# AntHab-Micro-12i.net
KiCad netlist of a schematic drawn in EAGLE
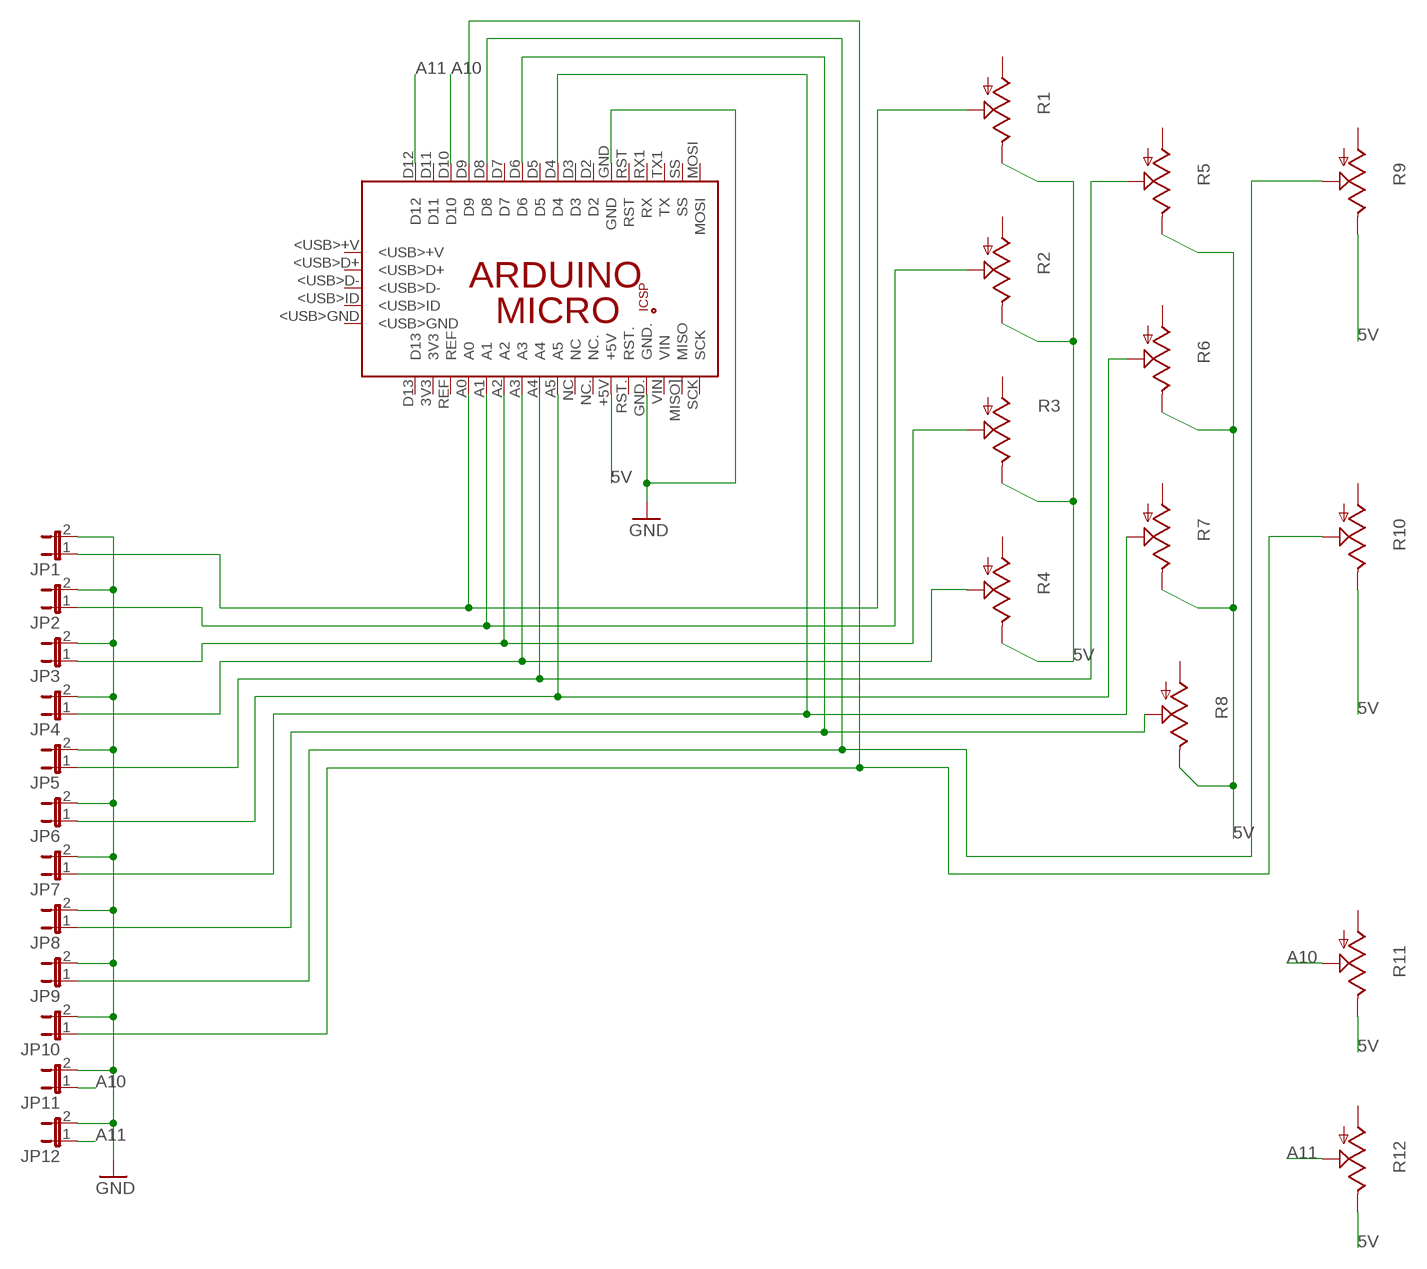
[diagram p0: schematic, sheet 1]

(export (version "E")
  (design (tool "Eeschema 10.0.6"))
  (components
    (comp (ref "JP1")
      (value "JP1E")
      (footprint "eagle-import:JP1")
      (libsource (lib "eagle-import") (part "JP1E"))
    )
    (comp (ref "JP2")
      (value "JP1E")
      (footprint "eagle-import:JP1")
      (libsource (lib "eagle-import") (part "JP1E"))
    )
    (comp (ref "JP3")
      (value "JP1E")
      (footprint "eagle-import:JP1")
      (libsource (lib "eagle-import") (part "JP1E"))
    )
    (comp (ref "JP4")
      (value "JP1E")
      (footprint "eagle-import:JP1")
      (libsource (lib "eagle-import") (part "JP1E"))
    )
    (comp (ref "JP5")
      (value "JP1E")
      (footprint "eagle-import:JP1")
      (libsource (lib "eagle-import") (part "JP1E"))
    )
    (comp (ref "JP6")
      (value "JP1E")
      (footprint "eagle-import:JP1")
      (libsource (lib "eagle-import") (part "JP1E"))
    )
    (comp (ref "JP7")
      (value "JP1E")
      (footprint "eagle-import:JP1")
      (libsource (lib "eagle-import") (part "JP1E"))
    )
    (comp (ref "JP8")
      (value "JP1E")
      (footprint "eagle-import:JP1")
      (libsource (lib "eagle-import") (part "JP1E"))
    )
    (comp (ref "JP9")
      (value "JP1E")
      (footprint "eagle-import:JP1")
      (libsource (lib "eagle-import") (part "JP1E"))
    )
    (comp (ref "JP10")
      (value "JP1E")
      (footprint "eagle-import:JP1")
      (libsource (lib "eagle-import") (part "JP1E"))
    )
    (comp (ref "JP11")
      (value "JP1E")
      (footprint "eagle-import:JP1")
      (libsource (lib "eagle-import") (part "JP1E"))
    )
    (comp (ref "JP12")
      (value "JP1E")
      (footprint "eagle-import:JP1")
      (libsource (lib "eagle-import") (part "JP1E"))
    )
    (comp (ref "PCB1")
      (value "ARDUINO_MICRO")
      (footprint "eagle-import:ARDUINO_MICRO")
      (libsource (lib "eagle-import") (part "ARDUINO_MICRO"))
    )
    (comp (ref "R1")
      (value "TRIM_US-CT6")
      (footprint "eagle-import:CT6")
      (libsource (lib "eagle-import") (part "TRIM_US-CT6"))
    )
    (comp (ref "R2")
      (value "TRIM_US-CT6")
      (footprint "eagle-import:CT6")
      (libsource (lib "eagle-import") (part "TRIM_US-CT6"))
    )
    (comp (ref "R3")
      (value "TRIM_US-CT6")
      (footprint "eagle-import:CT6")
      (libsource (lib "eagle-import") (part "TRIM_US-CT6"))
    )
    (comp (ref "R4")
      (value "TRIM_US-CT6")
      (footprint "eagle-import:CT6")
      (libsource (lib "eagle-import") (part "TRIM_US-CT6"))
    )
    (comp (ref "R5")
      (value "TRIM_US-CT6")
      (footprint "eagle-import:CT6")
      (libsource (lib "eagle-import") (part "TRIM_US-CT6"))
    )
    (comp (ref "R6")
      (value "TRIM_US-CT6")
      (footprint "eagle-import:CT6")
      (libsource (lib "eagle-import") (part "TRIM_US-CT6"))
    )
    (comp (ref "R7")
      (value "TRIM_US-CT6")
      (footprint "eagle-import:CT6")
      (libsource (lib "eagle-import") (part "TRIM_US-CT6"))
    )
    (comp (ref "R8")
      (value "TRIM_US-CT6")
      (footprint "eagle-import:CT6")
      (libsource (lib "eagle-import") (part "TRIM_US-CT6"))
    )
    (comp (ref "R9")
      (value "TRIM_US-CT6")
      (footprint "eagle-import:CT6")
      (libsource (lib "eagle-import") (part "TRIM_US-CT6"))
    )
    (comp (ref "R10")
      (value "TRIM_US-CT6")
      (footprint "eagle-import:CT6")
      (libsource (lib "eagle-import") (part "TRIM_US-CT6"))
    )
    (comp (ref "R11")
      (value "TRIM_US-CT6")
      (footprint "eagle-import:CT6")
      (libsource (lib "eagle-import") (part "TRIM_US-CT6"))
    )
    (comp (ref "R12")
      (value "TRIM_US-CT6")
      (footprint "eagle-import:CT6")
      (libsource (lib "eagle-import") (part "TRIM_US-CT6"))
    )
  )
  (nets
    (net (code "1") (name "/5V") (class "Default")
      (node (ref "PCB1") (pin "+5V") (pinfunction "+5V_+5V") (pintype "bidirectional"))
      (node (ref "R1") (pin "E") (pinfunction "E_E") (pintype "passive"))
      (node (ref "R10") (pin "E") (pinfunction "E_E") (pintype "passive"))
      (node (ref "R11") (pin "E") (pinfunction "E_E") (pintype "passive"))
      (node (ref "R12") (pin "E") (pinfunction "E_E") (pintype "passive"))
      (node (ref "R2") (pin "E") (pinfunction "E_E") (pintype "passive"))
      (node (ref "R3") (pin "E") (pinfunction "E_E") (pintype "passive"))
      (node (ref "R4") (pin "E") (pinfunction "E_E") (pintype "passive"))
      (node (ref "R5") (pin "E") (pinfunction "E_E") (pintype "passive"))
      (node (ref "R6") (pin "E") (pinfunction "E_E") (pintype "passive"))
      (node (ref "R7") (pin "E") (pinfunction "E_E") (pintype "passive"))
      (node (ref "R8") (pin "E") (pinfunction "E_E") (pintype "passive"))
      (node (ref "R9") (pin "E") (pinfunction "E_E") (pintype "passive"))
    )
    (net (code "2") (name "/A10") (class "Default")
      (node (ref "JP11") (pin "1") (pinfunction "1_1") (pintype "passive"))
      (node (ref "PCB1") (pin "D10") (pinfunction "D10_D10") (pintype "bidirectional"))
      (node (ref "R11") (pin "S") (pinfunction "S_S") (pintype "passive"))
    )
    (net (code "3") (name "/A11") (class "Default")
      (node (ref "JP12") (pin "1") (pinfunction "1_1") (pintype "passive"))
      (node (ref "PCB1") (pin "D12") (pinfunction "D12_D12") (pintype "bidirectional"))
      (node (ref "R12") (pin "S") (pinfunction "S_S") (pintype "passive"))
    )
    (net (code "4") (name "GND") (class "Default")
      (node (ref "JP1") (pin "2") (pinfunction "2_2") (pintype "passive"))
      (node (ref "JP10") (pin "2") (pinfunction "2_2") (pintype "passive"))
      (node (ref "JP11") (pin "2") (pinfunction "2_2") (pintype "passive"))
      (node (ref "JP12") (pin "2") (pinfunction "2_2") (pintype "passive"))
      (node (ref "JP2") (pin "2") (pinfunction "2_2") (pintype "passive"))
      (node (ref "JP3") (pin "2") (pinfunction "2_2") (pintype "passive"))
      (node (ref "JP4") (pin "2") (pinfunction "2_2") (pintype "passive"))
      (node (ref "JP5") (pin "2") (pinfunction "2_2") (pintype "passive"))
      (node (ref "JP6") (pin "2") (pinfunction "2_2") (pintype "passive"))
      (node (ref "JP7") (pin "2") (pinfunction "2_2") (pintype "passive"))
      (node (ref "JP8") (pin "2") (pinfunction "2_2") (pintype "passive"))
      (node (ref "JP9") (pin "2") (pinfunction "2_2") (pintype "passive"))
      (node (ref "PCB1") (pin "GND") (pinfunction "GND_GND") (pintype "bidirectional"))
      (node (ref "PCB1") (pin "GND.") (pinfunction "GND._GND.") (pintype "bidirectional"))
    )
    (net (code "5") (name "Net-(JP1-Pad1)") (class "Default")
      (node (ref "JP1") (pin "1") (pinfunction "1_1") (pintype "passive"))
      (node (ref "PCB1") (pin "A0") (pinfunction "A0_A0") (pintype "bidirectional"))
      (node (ref "R1") (pin "S") (pinfunction "S_S") (pintype "passive"))
    )
    (net (code "6") (name "Net-(JP2-Pad1)") (class "Default")
      (node (ref "JP2") (pin "1") (pinfunction "1_1") (pintype "passive"))
      (node (ref "PCB1") (pin "A1") (pinfunction "A1_A1") (pintype "bidirectional"))
      (node (ref "R2") (pin "S") (pinfunction "S_S") (pintype "passive"))
    )
    (net (code "7") (name "Net-(JP3-Pad1)") (class "Default")
      (node (ref "JP3") (pin "1") (pinfunction "1_1") (pintype "passive"))
      (node (ref "PCB1") (pin "A2") (pinfunction "A2_A2") (pintype "bidirectional"))
      (node (ref "R3") (pin "S") (pinfunction "S_S") (pintype "passive"))
    )
    (net (code "8") (name "Net-(JP4-Pad1)") (class "Default")
      (node (ref "JP4") (pin "1") (pinfunction "1_1") (pintype "passive"))
      (node (ref "PCB1") (pin "A3") (pinfunction "A3_A3") (pintype "bidirectional"))
      (node (ref "R4") (pin "S") (pinfunction "S_S") (pintype "passive"))
    )
    (net (code "9") (name "Net-(JP5-Pad1)") (class "Default")
      (node (ref "JP5") (pin "1") (pinfunction "1_1") (pintype "passive"))
      (node (ref "PCB1") (pin "A4") (pinfunction "A4_A4") (pintype "bidirectional"))
      (node (ref "R5") (pin "S") (pinfunction "S_S") (pintype "passive"))
    )
    (net (code "10") (name "Net-(JP6-Pad1)") (class "Default")
      (node (ref "JP6") (pin "1") (pinfunction "1_1") (pintype "passive"))
      (node (ref "PCB1") (pin "A5") (pinfunction "A5_A5") (pintype "bidirectional"))
      (node (ref "R6") (pin "S") (pinfunction "S_S") (pintype "passive"))
    )
    (net (code "11") (name "Net-(JP7-Pad1)") (class "Default")
      (node (ref "JP7") (pin "1") (pinfunction "1_1") (pintype "passive"))
      (node (ref "PCB1") (pin "D4") (pinfunction "D4_D4") (pintype "bidirectional"))
      (node (ref "R7") (pin "S") (pinfunction "S_S") (pintype "passive"))
    )
    (net (code "12") (name "Net-(JP8-Pad1)") (class "Default")
      (node (ref "JP8") (pin "1") (pinfunction "1_1") (pintype "passive"))
      (node (ref "PCB1") (pin "D6") (pinfunction "D6_D6") (pintype "bidirectional"))
      (node (ref "R8") (pin "S") (pinfunction "S_S") (pintype "passive"))
    )
    (net (code "13") (name "Net-(JP9-Pad1)") (class "Default")
      (node (ref "JP9") (pin "1") (pinfunction "1_1") (pintype "passive"))
      (node (ref "PCB1") (pin "D8") (pinfunction "D8_D8") (pintype "bidirectional"))
      (node (ref "R9") (pin "S") (pinfunction "S_S") (pintype "passive"))
    )
    (net (code "14") (name "Net-(JP10-Pad1)") (class "Default")
      (node (ref "JP10") (pin "1") (pinfunction "1_1") (pintype "passive"))
      (node (ref "PCB1") (pin "D9") (pinfunction "D9_D9") (pintype "bidirectional"))
      (node (ref "R10") (pin "S") (pinfunction "S_S") (pintype "passive"))
    )
    (net (code "15") (name "unconnected-(PCB1-MISO-PadMISO])") (class "Default")
      (node (ref "PCB1") (pin "MISO]") (pinfunction "MISO_MISO]") (pintype "bidirectional"))
    )
    (net (code "16") (name "unconnected-(PCB1-Pad3V3)") (class "Default")
      (node (ref "PCB1") (pin "3V3") (pinfunction "3V3_3V3") (pintype "bidirectional"))
    )
    (net (code "17") (name "unconnected-(PCB1-Pad5V)") (class "Default")
      (node (ref "PCB1") (pin "5V") (pinfunction "5V_5V") (pintype "bidirectional"))
    )
    (net (code "18") (name "unconnected-(PCB1-Pad<USB>+V)") (class "Default")
      (node (ref "PCB1") (pin "<USB>+V") (pinfunction "<USB>+V_<USB>+V") (pintype "bidirectional"))
    )
    (net (code "19") (name "unconnected-(PCB1-Pad<USB>D+)") (class "Default")
      (node (ref "PCB1") (pin "<USB>D+") (pinfunction "<USB>D+_<USB>D+") (pintype "bidirectional"))
    )
    (net (code "20") (name "unconnected-(PCB1-Pad<USB>D-)") (class "Default")
      (node (ref "PCB1") (pin "<USB>D-") (pinfunction "<USB>D-_<USB>D-") (pintype "bidirectional"))
    )
    (net (code "21") (name "unconnected-(PCB1-Pad<USB>GND)") (class "Default")
      (node (ref "PCB1") (pin "<USB>GND") (pinfunction "<USB>GND_<USB>GND") (pintype "bidirectional"))
    )
    (net (code "22") (name "unconnected-(PCB1-Pad<USB>ID)") (class "Default")
      (node (ref "PCB1") (pin "<USB>ID") (pinfunction "<USB>ID_<USB>ID") (pintype "bidirectional"))
    )
    (net (code "23") (name "unconnected-(PCB1-PadD2)") (class "Default")
      (node (ref "PCB1") (pin "D2") (pinfunction "D2_D2") (pintype "bidirectional"))
    )
    (net (code "24") (name "unconnected-(PCB1-PadD3)") (class "Default")
      (node (ref "PCB1") (pin "D3") (pinfunction "D3_D3") (pintype "bidirectional"))
    )
    (net (code "25") (name "unconnected-(PCB1-PadD5)") (class "Default")
      (node (ref "PCB1") (pin "D5") (pinfunction "D5_D5") (pintype "bidirectional"))
    )
    (net (code "26") (name "unconnected-(PCB1-PadD7)") (class "Default")
      (node (ref "PCB1") (pin "D7") (pinfunction "D7_D7") (pintype "bidirectional"))
    )
    (net (code "27") (name "unconnected-(PCB1-PadD11)") (class "Default")
      (node (ref "PCB1") (pin "D11") (pinfunction "D11_D11") (pintype "bidirectional"))
    )
    (net (code "28") (name "unconnected-(PCB1-PadD13)") (class "Default")
      (node (ref "PCB1") (pin "D13") (pinfunction "D13_D13") (pintype "bidirectional"))
    )
    (net (code "29") (name "unconnected-(PCB1-PadGND_)") (class "Default")
      (node (ref "PCB1") (pin "GND_") (pinfunction "GND__GND_") (pintype "bidirectional"))
    )
    (net (code "30") (name "unconnected-(PCB1-PadMISO.)") (class "Default")
      (node (ref "PCB1") (pin "MISO.") (pinfunction "MISO._MISO.") (pintype "bidirectional"))
    )
    (net (code "31") (name "unconnected-(PCB1-PadMOSI)") (class "Default")
      (node (ref "PCB1") (pin "MOSI") (pinfunction "MOSI_MOSI") (pintype "bidirectional"))
    )
    (net (code "32") (name "unconnected-(PCB1-PadMOSI.)") (class "Default")
      (node (ref "PCB1") (pin "MOSI.") (pinfunction "MOSI._MOSI.") (pintype "bidirectional"))
    )
    (net (code "33") (name "unconnected-(PCB1-PadNC)") (class "Default")
      (node (ref "PCB1") (pin "NC") (pinfunction "NC_NC") (pintype "bidirectional"))
    )
    (net (code "34") (name "unconnected-(PCB1-PadNC.)") (class "Default")
      (node (ref "PCB1") (pin "NC.") (pinfunction "NC._NC.") (pintype "bidirectional"))
    )
    (net (code "35") (name "unconnected-(PCB1-PadREF)") (class "Default")
      (node (ref "PCB1") (pin "REF") (pinfunction "REF_REF") (pintype "bidirectional"))
    )
    (net (code "36") (name "unconnected-(PCB1-PadRESET..)") (class "Default")
      (node (ref "PCB1") (pin "RESET..") (pinfunction "RESET.._RESET..") (pintype "bidirectional"))
    )
    (net (code "37") (name "unconnected-(PCB1-PadRST)") (class "Default")
      (node (ref "PCB1") (pin "RST") (pinfunction "RST_RST") (pintype "bidirectional"))
    )
    (net (code "38") (name "unconnected-(PCB1-PadRST.)") (class "Default")
      (node (ref "PCB1") (pin "RST.") (pinfunction "RST._RST.") (pintype "bidirectional"))
    )
    (net (code "39") (name "unconnected-(PCB1-PadSCK)") (class "Default")
      (node (ref "PCB1") (pin "SCK") (pinfunction "SCK_SCK") (pintype "bidirectional"))
    )
    (net (code "40") (name "unconnected-(PCB1-PadSCK.)") (class "Default")
      (node (ref "PCB1") (pin "SCK.") (pinfunction "SCK._SCK.") (pintype "bidirectional"))
    )
    (net (code "41") (name "unconnected-(PCB1-PadSS)") (class "Default")
      (node (ref "PCB1") (pin "SS") (pinfunction "SS_SS") (pintype "bidirectional"))
    )
    (net (code "42") (name "unconnected-(PCB1-PadVIN)") (class "Default")
      (node (ref "PCB1") (pin "VIN") (pinfunction "VIN_VIN") (pintype "bidirectional"))
    )
    (net (code "43") (name "unconnected-(PCB1-RX-PadRX1)") (class "Default")
      (node (ref "PCB1") (pin "RX1") (pinfunction "RX_RX1") (pintype "bidirectional"))
    )
    (net (code "44") (name "unconnected-(PCB1-TX-PadTX1)") (class "Default")
      (node (ref "PCB1") (pin "TX1") (pinfunction "TX_TX1") (pintype "bidirectional"))
    )
    (net (code "45") (name "unconnected-(R1-PadA)") (class "Default")
      (node (ref "R1") (pin "A") (pinfunction "A_A") (pintype "passive"))
    )
    (net (code "46") (name "unconnected-(R2-PadA)") (class "Default")
      (node (ref "R2") (pin "A") (pinfunction "A_A") (pintype "passive"))
    )
    (net (code "47") (name "unconnected-(R3-PadA)") (class "Default")
      (node (ref "R3") (pin "A") (pinfunction "A_A") (pintype "passive"))
    )
    (net (code "48") (name "unconnected-(R4-PadA)") (class "Default")
      (node (ref "R4") (pin "A") (pinfunction "A_A") (pintype "passive"))
    )
    (net (code "49") (name "unconnected-(R5-PadA)") (class "Default")
      (node (ref "R5") (pin "A") (pinfunction "A_A") (pintype "passive"))
    )
    (net (code "50") (name "unconnected-(R6-PadA)") (class "Default")
      (node (ref "R6") (pin "A") (pinfunction "A_A") (pintype "passive"))
    )
    (net (code "51") (name "unconnected-(R7-PadA)") (class "Default")
      (node (ref "R7") (pin "A") (pinfunction "A_A") (pintype "passive"))
    )
    (net (code "52") (name "unconnected-(R8-PadA)") (class "Default")
      (node (ref "R8") (pin "A") (pinfunction "A_A") (pintype "passive"))
    )
    (net (code "53") (name "unconnected-(R9-PadA)") (class "Default")
      (node (ref "R9") (pin "A") (pinfunction "A_A") (pintype "passive"))
    )
    (net (code "54") (name "unconnected-(R10-PadA)") (class "Default")
      (node (ref "R10") (pin "A") (pinfunction "A_A") (pintype "passive"))
    )
    (net (code "55") (name "unconnected-(R11-PadA)") (class "Default")
      (node (ref "R11") (pin "A") (pinfunction "A_A") (pintype "passive"))
    )
    (net (code "56") (name "unconnected-(R12-PadA)") (class "Default")
      (node (ref "R12") (pin "A") (pinfunction "A_A") (pintype "passive"))
    )
  )
)
